# X13-Isolation.net
KiCad netlist of a schematic drawn in Altium Designer
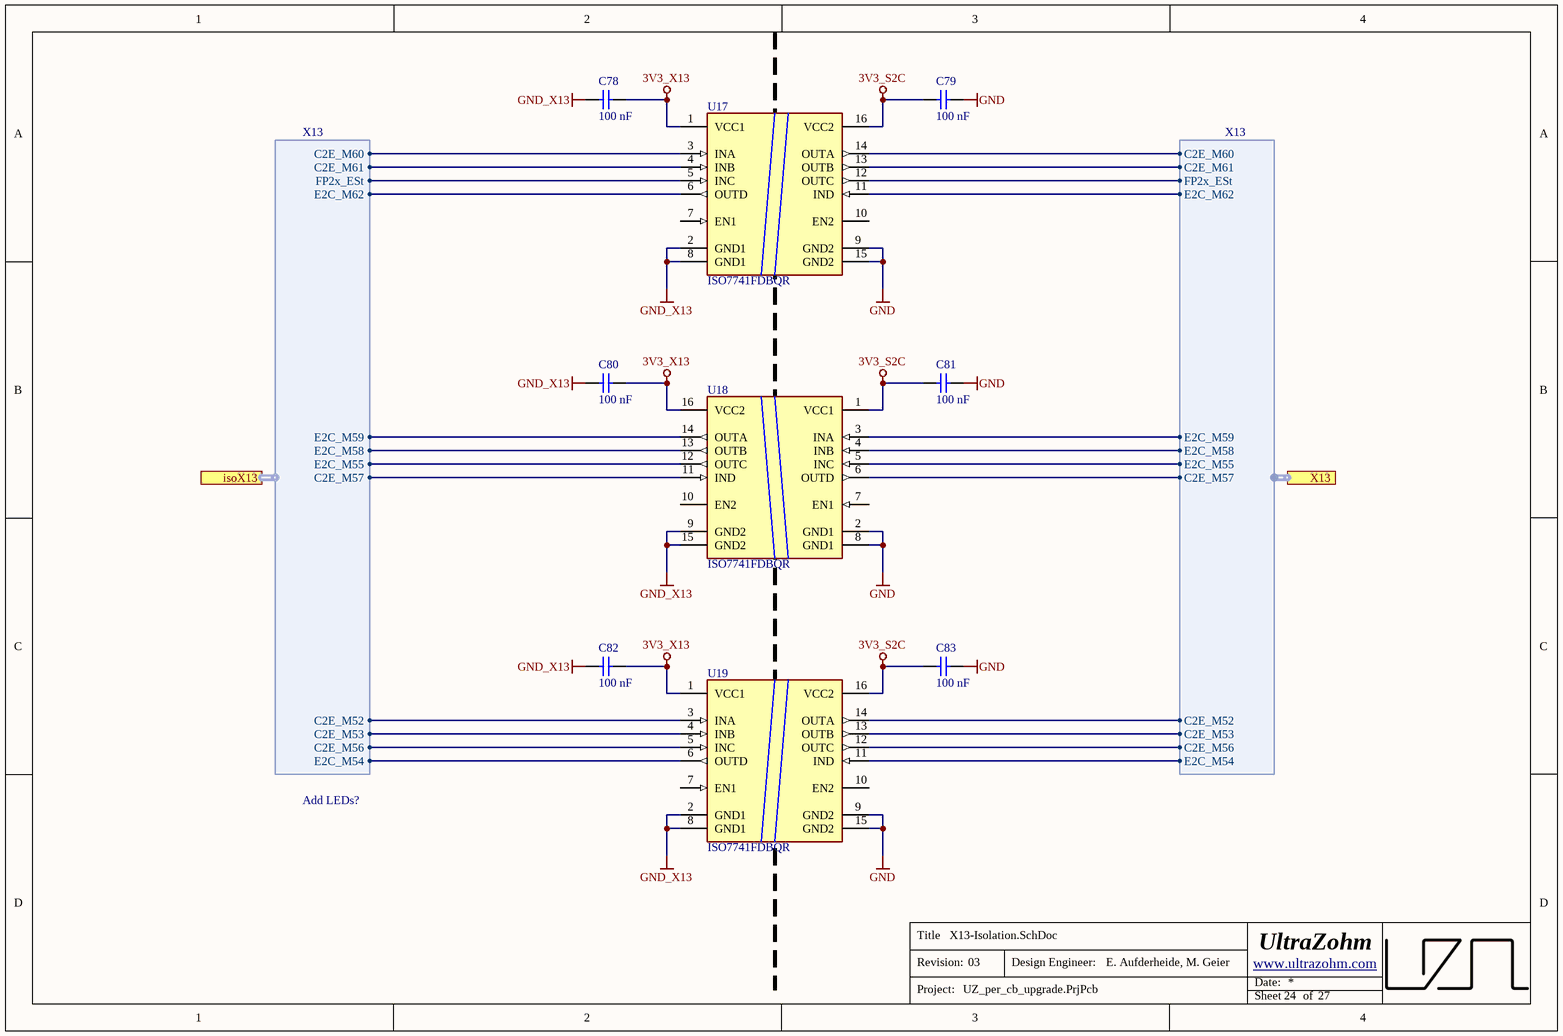
[diagram p0: X13-Isolation.SchDoc]

(export (version "E")
  (design (tool "Eeschema 10.0.6"))
  (components
    (comp (ref "C78")
      (value "100 nF")
      (footprint "C_0603_TE")
      (description "Generic capacitor")
      (fields
        (field (name "MANUFACTURER PART NUMBER") "UZgen_C_0603_100nF_50V_X7R")
        (field (name "MANUFACTURER") "UZgen")
        (field (name "CREATED FROM") "AGeiger")
      )
      (libsource (lib "user") (part "CAP-NP"))
    )
    (comp (ref "C79")
      (value "100 nF")
      (footprint "C_0603_TE")
      (description "Generic capacitor")
      (fields
        (field (name "MANUFACTURER PART NUMBER") "UZgen_C_0603_100nF_50V_X7R")
        (field (name "MANUFACTURER") "UZgen")
        (field (name "CREATED FROM") "AGeiger")
      )
      (libsource (lib "user") (part "CAP-NP"))
    )
    (comp (ref "C80")
      (value "100 nF")
      (footprint "C_0603_TE")
      (description "Generic capacitor")
      (fields
        (field (name "MANUFACTURER PART NUMBER") "UZgen_C_0603_100nF_50V_X7R")
        (field (name "MANUFACTURER") "UZgen")
        (field (name "CREATED FROM") "AGeiger")
      )
      (libsource (lib "user") (part "CAP-NP"))
    )
    (comp (ref "C81")
      (value "100 nF")
      (footprint "C_0603_TE")
      (description "Generic capacitor")
      (fields
        (field (name "MANUFACTURER PART NUMBER") "UZgen_C_0603_100nF_50V_X7R")
        (field (name "MANUFACTURER") "UZgen")
        (field (name "CREATED FROM") "AGeiger")
      )
      (libsource (lib "user") (part "CAP-NP"))
    )
    (comp (ref "C82")
      (value "100 nF")
      (footprint "C_0603_TE")
      (description "Generic capacitor")
      (fields
        (field (name "MANUFACTURER PART NUMBER") "UZgen_C_0603_100nF_50V_X7R")
        (field (name "MANUFACTURER") "UZgen")
        (field (name "CREATED FROM") "AGeiger")
      )
      (libsource (lib "user") (part "CAP-NP"))
    )
    (comp (ref "C83")
      (value "100 nF")
      (footprint "C_0603_TE")
      (description "Generic capacitor")
      (fields
        (field (name "MANUFACTURER PART NUMBER") "UZgen_C_0603_100nF_50V_X7R")
        (field (name "MANUFACTURER") "UZgen")
        (field (name "CREATED FROM") "AGeiger")
      )
      (libsource (lib "user") (part "CAP-NP"))
    )
    (comp (ref "U17")
      (value "ISO7741FDBQR")
      (footprint "SOP64P600X175-16N")
      (description "ISO774xT-Q1 High-Speed, Reinforced Quad-Channel Digital Isolators With Integrated")
      (fields
        (field (name "MANUFACTURER") "Texas Instruments")
        (field (name "LCSC PART NUMBER") "C2872241")
        (field (name "CREATED FROM") "FRosner")
      )
      (libsource (lib "user") (part "ISO7741"))
    )
    (comp (ref "U18")
      (value "ISO7741FDBQR")
      (footprint "SOP64P600X175-16N")
      (description "ISO774xT-Q1 High-Speed, Reinforced Quad-Channel Digital Isolators With Integrated")
      (fields
        (field (name "MANUFACTURER") "Texas Instruments")
        (field (name "LCSC PART NUMBER") "C2872241")
        (field (name "CREATED FROM") "FRosner")
      )
      (libsource (lib "") (part "ISO7741_1"))
    )
    (comp (ref "U19")
      (value "ISO7741FDBQR")
      (footprint "SOP64P600X175-16N")
      (description "ISO774xT-Q1 High-Speed, Reinforced Quad-Channel Digital Isolators With Integrated")
      (fields
        (field (name "MANUFACTURER") "Texas Instruments")
        (field (name "LCSC PART NUMBER") "C2872241")
        (field (name "CREATED FROM") "FRosner")
      )
      (libsource (lib "user") (part "ISO7741"))
    )
  )
  (nets
    (net (code "3") (name "3V3_S2C") (class "Default")
      (node (ref "C79") (pin "2") (pinfunction "2_2") (pintype "passive"))
      (node (ref "C81") (pin "2") (pinfunction "2_2") (pintype "passive"))
      (node (ref "C83") (pin "2") (pinfunction "2_2") (pintype "passive"))
      (node (ref "U17") (pin "16") (pinfunction "VCC2_16") (pintype "passive"))
      (node (ref "U18") (pin "1") (pinfunction "VCC1_1") (pintype "passive"))
      (node (ref "U19") (pin "16") (pinfunction "VCC2_16") (pintype "passive"))
    )
    (net (code "4") (name "3V3_X13") (class "Default")
      (node (ref "C78") (pin "1") (pinfunction "1_1") (pintype "passive"))
      (node (ref "C80") (pin "1") (pinfunction "1_1") (pintype "passive"))
      (node (ref "C82") (pin "1") (pinfunction "1_1") (pintype "passive"))
      (node (ref "U17") (pin "1") (pinfunction "VCC1_1") (pintype "passive"))
      (node (ref "U18") (pin "16") (pinfunction "VCC2_16") (pintype "passive"))
      (node (ref "U19") (pin "1") (pinfunction "VCC1_1") (pintype "passive"))
    )
    (net (code "5") (name "GND") (class "Default")
      (node (ref "C79") (pin "1") (pinfunction "1_1") (pintype "passive"))
      (node (ref "C81") (pin "1") (pinfunction "1_1") (pintype "passive"))
      (node (ref "C83") (pin "1") (pinfunction "1_1") (pintype "passive"))
      (node (ref "U17") (pin "15") (pinfunction "GND2_15") (pintype "passive"))
      (node (ref "U17") (pin "9") (pinfunction "GND2_9") (pintype "passive"))
      (node (ref "U18") (pin "2") (pinfunction "GND1_2") (pintype "passive"))
      (node (ref "U18") (pin "8") (pinfunction "GND1_8") (pintype "passive"))
      (node (ref "U19") (pin "15") (pinfunction "GND2_15") (pintype "passive"))
      (node (ref "U19") (pin "9") (pinfunction "GND2_9") (pintype "passive"))
    )
    (net (code "6") (name "GND_X13") (class "Default")
      (node (ref "C78") (pin "2") (pinfunction "2_2") (pintype "passive"))
      (node (ref "C80") (pin "2") (pinfunction "2_2") (pintype "passive"))
      (node (ref "C82") (pin "2") (pinfunction "2_2") (pintype "passive"))
      (node (ref "U17") (pin "2") (pinfunction "GND1_2") (pintype "passive"))
      (node (ref "U17") (pin "8") (pinfunction "GND1_8") (pintype "passive"))
      (node (ref "U18") (pin "15") (pinfunction "GND2_15") (pintype "passive"))
      (node (ref "U18") (pin "9") (pinfunction "GND2_9") (pintype "passive"))
      (node (ref "U19") (pin "2") (pinfunction "GND1_2") (pintype "passive"))
      (node (ref "U19") (pin "8") (pinfunction "GND1_8") (pintype "passive"))
    )
    (net (code "7") (name "unconnected-(U17-EN1-Pad7)") (class "Default")
      (node (ref "U17") (pin "7") (pinfunction "EN1_7") (pintype "input"))
    )
    (net (code "8") (name "unconnected-(U17-EN2-Pad10)") (class "Default")
      (node (ref "U17") (pin "10") (pinfunction "EN2_10") (pintype "passive"))
    )
    (net (code "9") (name "unconnected-(U17-INA-Pad3)") (class "Default")
      (node (ref "U17") (pin "3") (pinfunction "INA_3") (pintype "input"))
    )
    (net (code "10") (name "unconnected-(U17-INB-Pad4)") (class "Default")
      (node (ref "U17") (pin "4") (pinfunction "INB_4") (pintype "input"))
    )
    (net (code "11") (name "unconnected-(U17-INC-Pad5)") (class "Default")
      (node (ref "U17") (pin "5") (pinfunction "INC_5") (pintype "input"))
    )
    (net (code "12") (name "unconnected-(U17-IND-Pad11)") (class "Default")
      (node (ref "U17") (pin "11") (pinfunction "IND_11") (pintype "input"))
    )
    (net (code "13") (name "unconnected-(U17-OUTA-Pad14)") (class "Default")
      (node (ref "U17") (pin "14") (pinfunction "OUTA_14") (pintype "output"))
    )
    (net (code "14") (name "unconnected-(U17-OUTB-Pad13)") (class "Default")
      (node (ref "U17") (pin "13") (pinfunction "OUTB_13") (pintype "output"))
    )
    (net (code "15") (name "unconnected-(U17-OUTC-Pad12)") (class "Default")
      (node (ref "U17") (pin "12") (pinfunction "OUTC_12") (pintype "output"))
    )
    (net (code "16") (name "unconnected-(U17-OUTD-Pad6)") (class "Default")
      (node (ref "U17") (pin "6") (pinfunction "OUTD_6") (pintype "output"))
    )
    (net (code "17") (name "unconnected-(U18-EN1-Pad7)") (class "Default")
      (node (ref "U18") (pin "7") (pinfunction "EN1_7") (pintype "input"))
    )
    (net (code "18") (name "unconnected-(U18-EN2-Pad10)") (class "Default")
      (node (ref "U18") (pin "10") (pinfunction "EN2_10") (pintype "passive"))
    )
    (net (code "19") (name "unconnected-(U18-INA-Pad3)") (class "Default")
      (node (ref "U18") (pin "3") (pinfunction "INA_3") (pintype "input"))
    )
    (net (code "20") (name "unconnected-(U18-INB-Pad4)") (class "Default")
      (node (ref "U18") (pin "4") (pinfunction "INB_4") (pintype "input"))
    )
    (net (code "21") (name "unconnected-(U18-INC-Pad5)") (class "Default")
      (node (ref "U18") (pin "5") (pinfunction "INC_5") (pintype "input"))
    )
    (net (code "22") (name "unconnected-(U18-IND-Pad11)") (class "Default")
      (node (ref "U18") (pin "11") (pinfunction "IND_11") (pintype "input"))
    )
    (net (code "23") (name "unconnected-(U18-OUTA-Pad14)") (class "Default")
      (node (ref "U18") (pin "14") (pinfunction "OUTA_14") (pintype "output"))
    )
    (net (code "24") (name "unconnected-(U18-OUTB-Pad13)") (class "Default")
      (node (ref "U18") (pin "13") (pinfunction "OUTB_13") (pintype "output"))
    )
    (net (code "25") (name "unconnected-(U18-OUTC-Pad12)") (class "Default")
      (node (ref "U18") (pin "12") (pinfunction "OUTC_12") (pintype "output"))
    )
    (net (code "26") (name "unconnected-(U18-OUTD-Pad6)") (class "Default")
      (node (ref "U18") (pin "6") (pinfunction "OUTD_6") (pintype "output"))
    )
    (net (code "27") (name "unconnected-(U19-EN1-Pad7)") (class "Default")
      (node (ref "U19") (pin "7") (pinfunction "EN1_7") (pintype "input"))
    )
    (net (code "28") (name "unconnected-(U19-EN2-Pad10)") (class "Default")
      (node (ref "U19") (pin "10") (pinfunction "EN2_10") (pintype "passive"))
    )
    (net (code "29") (name "unconnected-(U19-INA-Pad3)") (class "Default")
      (node (ref "U19") (pin "3") (pinfunction "INA_3") (pintype "input"))
    )
    (net (code "30") (name "unconnected-(U19-INB-Pad4)") (class "Default")
      (node (ref "U19") (pin "4") (pinfunction "INB_4") (pintype "input"))
    )
    (net (code "31") (name "unconnected-(U19-INC-Pad5)") (class "Default")
      (node (ref "U19") (pin "5") (pinfunction "INC_5") (pintype "input"))
    )
    (net (code "32") (name "unconnected-(U19-IND-Pad11)") (class "Default")
      (node (ref "U19") (pin "11") (pinfunction "IND_11") (pintype "input"))
    )
    (net (code "33") (name "unconnected-(U19-OUTA-Pad14)") (class "Default")
      (node (ref "U19") (pin "14") (pinfunction "OUTA_14") (pintype "output"))
    )
    (net (code "34") (name "unconnected-(U19-OUTB-Pad13)") (class "Default")
      (node (ref "U19") (pin "13") (pinfunction "OUTB_13") (pintype "output"))
    )
    (net (code "35") (name "unconnected-(U19-OUTC-Pad12)") (class "Default")
      (node (ref "U19") (pin "12") (pinfunction "OUTC_12") (pintype "output"))
    )
    (net (code "36") (name "unconnected-(U19-OUTD-Pad6)") (class "Default")
      (node (ref "U19") (pin "6") (pinfunction "OUTD_6") (pintype "output"))
    )
  )
)
